# gal-psg-2.net
KiCad netlist of a schematic drawn in EAGLE
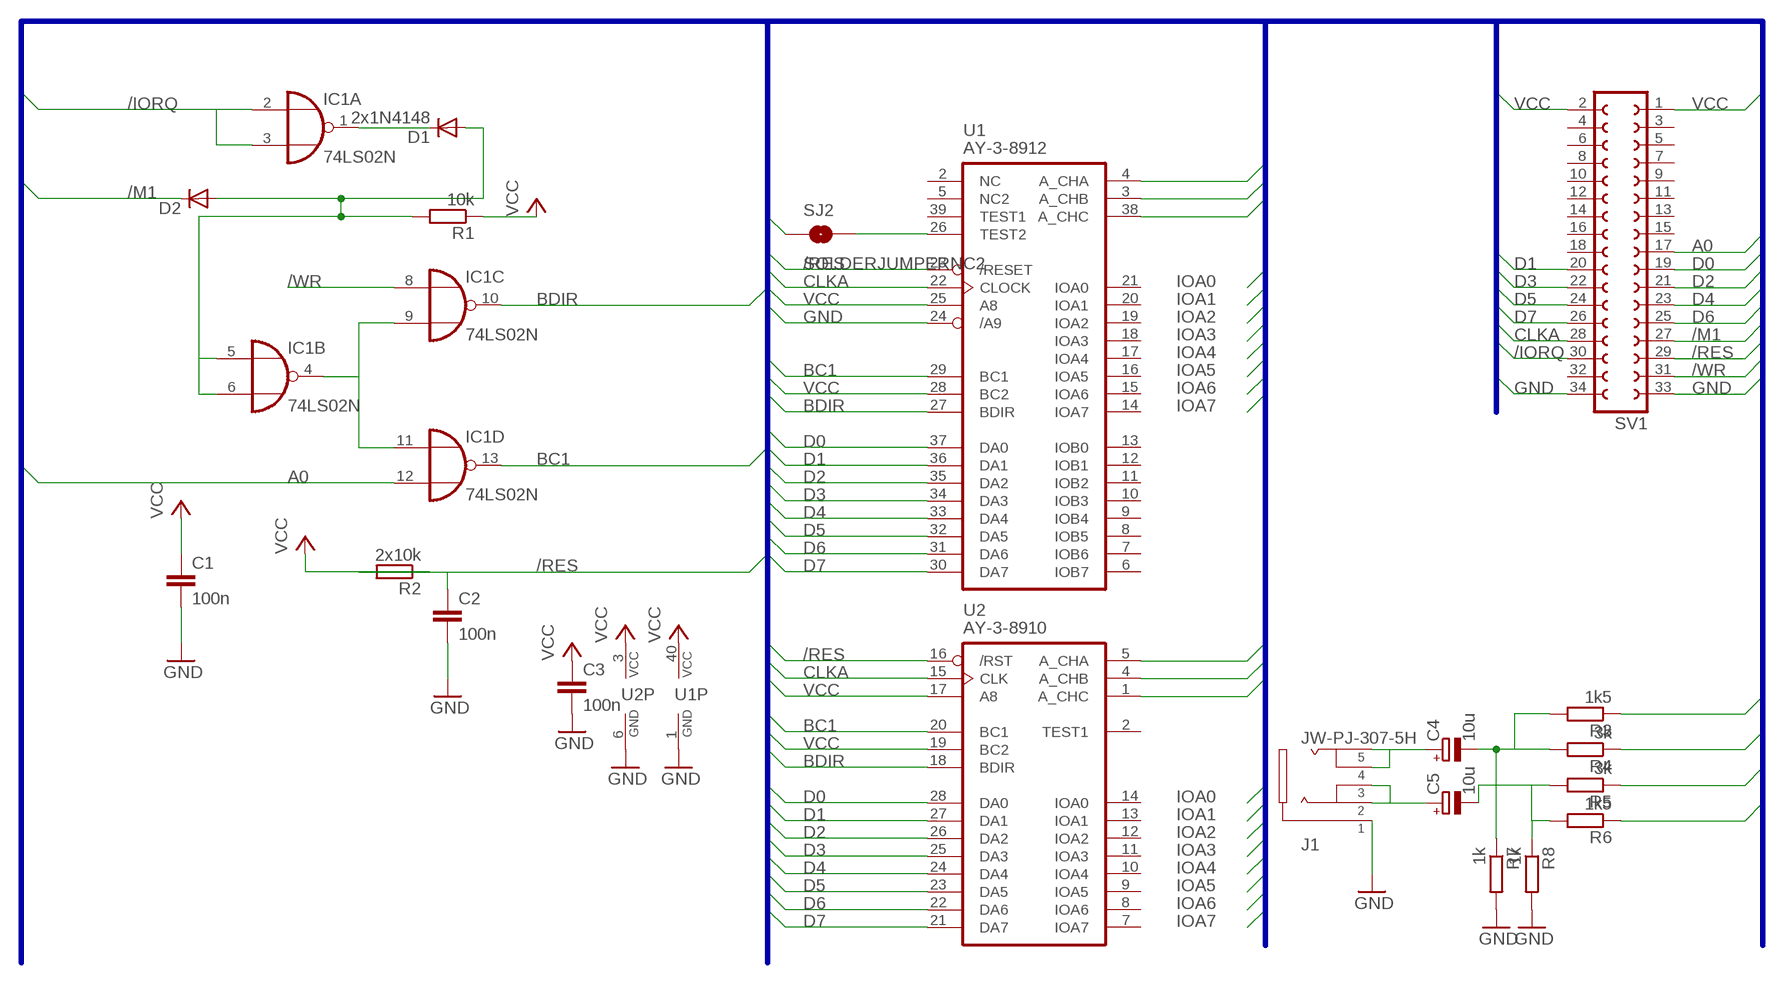
[diagram p0: schematic, sheet 1]

(export (version "E")
  (design (tool "Eeschema 10.0.6"))
  (components
    (comp (ref "C1")
      (value "100n")
      (footprint "eagle-import:C025-024X044")
      (libsource (lib "eagle-import") (part "C-EU025-024X044"))
    )
    (comp (ref "C2")
      (value "100n")
      (footprint "eagle-import:C025-024X044")
      (libsource (lib "eagle-import") (part "C-EU025-024X044"))
    )
    (comp (ref "C3")
      (value "100n")
      (footprint "eagle-import:C025-024X044")
      (libsource (lib "eagle-import") (part "C-EU025-024X044"))
    )
    (comp (ref "C4")
      (value "10u")
      (footprint "eagle-import:E1,8-4")
      (libsource (lib "eagle-import") (part "CPOL-EUE1.8-4"))
    )
    (comp (ref "C5")
      (value "10u")
      (footprint "eagle-import:E1,8-4")
      (libsource (lib "eagle-import") (part "CPOL-EUE1.8-4"))
    )
    (comp (ref "D1")
      (value "2x1N4148")
      (footprint "eagle-import:D-2.5")
      (libsource (lib "eagle-import") (part "DIODE-D-2.5"))
    )
    (comp (ref "D2")
      (value "DIODE-D-2.5")
      (footprint "eagle-import:D-2.5")
      (libsource (lib "eagle-import") (part "DIODE-D-2.5"))
    )
    (comp (ref "IC1")
      (value "74LS02N")
      (footprint "eagle-import:DIL14")
      (libsource (lib "eagle-import") (part "7402NLS"))
    )
    (comp (ref "J1")
      (value "JW-PJ-307-5H")
      (footprint "eagle-import:JW-PJ-307-5H")
      (libsource (lib "eagle-import") (part "JW-PJ-307-5H"))
    )
    (comp (ref "R1")
      (value "10k")
      (footprint "eagle-import:0207_2V")
      (libsource (lib "eagle-import") (part "R-EU_0207/2V"))
    )
    (comp (ref "R2")
      (value "2x10k")
      (footprint "eagle-import:0207_2V")
      (libsource (lib "eagle-import") (part "R-EU_0207/2V"))
    )
    (comp (ref "R3")
      (value "1k5")
      (footprint "eagle-import:0207_2V")
      (libsource (lib "eagle-import") (part "R-EU_0207/2V"))
    )
    (comp (ref "R4")
      (value "3k")
      (footprint "eagle-import:0207_2V")
      (libsource (lib "eagle-import") (part "R-EU_0207/2V"))
    )
    (comp (ref "R5")
      (value "3k")
      (footprint "eagle-import:0207_2V")
      (libsource (lib "eagle-import") (part "R-EU_0207/2V"))
    )
    (comp (ref "R6")
      (value "1k5")
      (footprint "eagle-import:0207_2V")
      (libsource (lib "eagle-import") (part "R-EU_0207/2V"))
    )
    (comp (ref "R7")
      (value "1k")
      (footprint "eagle-import:0207_2V")
      (libsource (lib "eagle-import") (part "R-EU_0207/2V"))
    )
    (comp (ref "R8")
      (value "1k")
      (footprint "eagle-import:0207_2V")
      (libsource (lib "eagle-import") (part "R-EU_0207/2V"))
    )
    (comp (ref "SJ2")
      (value "SOLDERJUMPERNC2")
      (footprint "eagle-import:SJ_2S-NOTRACE")
      (libsource (lib "eagle-import") (part "SOLDERJUMPERNC2"))
    )
    (comp (ref "SV1")
      (value "FE17-2W")
      (footprint "eagle-import:FE17-2W")
      (libsource (lib "eagle-import") (part "FE17-2W"))
    )
    (comp (ref "U1")
      (value "AY-3-8912")
      (footprint "eagle-import:DIL40")
      (libsource (lib "eagle-import") (part "AY-3-8912"))
    )
    (comp (ref "U2")
      (value "AY-3-8910")
      (footprint "eagle-import:DIL28-6")
      (libsource (lib "eagle-import") (part "AY-3-8910"))
    )
  )
  (nets
    (net (code "1") (name "/A") (class "Default")
      (node (ref "R3") (pin "1") (pinfunction "1_1") (pintype "passive"))
      (node (ref "U1") (pin "4") (pinfunction "A_CHA_4") (pintype "output"))
      (node (ref "U2") (pin "5") (pinfunction "A_CHA_5") (pintype "output"))
    )
    (net (code "2") (name "/A0") (class "Default")
      (node (ref "IC1") (pin "12") (pinfunction "I1_12") (pintype "input"))
      (node (ref "SV1") (pin "17") (pinfunction "17_17") (pintype "passive"))
    )
    (net (code "3") (name "/B") (class "Default")
      (node (ref "R4") (pin "1") (pinfunction "1_1") (pintype "passive"))
      (node (ref "R5") (pin "1") (pinfunction "1_1") (pintype "passive"))
      (node (ref "U1") (pin "3") (pinfunction "A_CHB_3") (pintype "output"))
      (node (ref "U2") (pin "4") (pinfunction "A_CHB_4") (pintype "output"))
    )
    (net (code "4") (name "/BC1") (class "Default")
      (node (ref "IC1") (pin "13") (pinfunction "O_13") (pintype "output"))
      (node (ref "U1") (pin "29") (pinfunction "BC1_29") (pintype "input"))
      (node (ref "U2") (pin "20") (pinfunction "BC1_20") (pintype "input"))
    )
    (net (code "5") (name "/BDIR") (class "Default")
      (node (ref "IC1") (pin "10") (pinfunction "O_10") (pintype "output"))
      (node (ref "U1") (pin "27") (pinfunction "BDIR_27") (pintype "input"))
      (node (ref "U2") (pin "18") (pinfunction "BDIR_18") (pintype "input"))
    )
    (net (code "6") (name "/C") (class "Default")
      (node (ref "R6") (pin "1") (pinfunction "1_1") (pintype "passive"))
      (node (ref "U1") (pin "38") (pinfunction "A_CHC_38") (pintype "output"))
      (node (ref "U2") (pin "1") (pinfunction "A_CHC_1") (pintype "output"))
    )
    (net (code "7") (name "/CLKA") (class "Default")
      (node (ref "SV1") (pin "28") (pinfunction "28_28") (pintype "passive"))
      (node (ref "U1") (pin "22") (pinfunction "CLOCK_22") (pintype "input"))
      (node (ref "U2") (pin "15") (pinfunction "CLK_15") (pintype "input"))
    )
    (net (code "8") (name "/D0") (class "Default")
      (node (ref "SV1") (pin "19") (pinfunction "19_19") (pintype "passive"))
      (node (ref "U1") (pin "37") (pinfunction "DA0_37") (pintype "bidirectional"))
      (node (ref "U2") (pin "28") (pinfunction "DA0_28") (pintype "bidirectional"))
    )
    (net (code "9") (name "/D1") (class "Default")
      (node (ref "SV1") (pin "20") (pinfunction "20_20") (pintype "passive"))
      (node (ref "U1") (pin "36") (pinfunction "DA1_36") (pintype "bidirectional"))
      (node (ref "U2") (pin "27") (pinfunction "DA1_27") (pintype "bidirectional"))
    )
    (net (code "10") (name "/D2") (class "Default")
      (node (ref "SV1") (pin "21") (pinfunction "21_21") (pintype "passive"))
      (node (ref "U1") (pin "35") (pinfunction "DA2_35") (pintype "bidirectional"))
      (node (ref "U2") (pin "26") (pinfunction "DA2_26") (pintype "bidirectional"))
    )
    (net (code "11") (name "/D3") (class "Default")
      (node (ref "SV1") (pin "22") (pinfunction "22_22") (pintype "passive"))
      (node (ref "U1") (pin "34") (pinfunction "DA3_34") (pintype "bidirectional"))
      (node (ref "U2") (pin "25") (pinfunction "DA3_25") (pintype "bidirectional"))
    )
    (net (code "12") (name "/D4") (class "Default")
      (node (ref "SV1") (pin "23") (pinfunction "23_23") (pintype "passive"))
      (node (ref "U1") (pin "33") (pinfunction "DA4_33") (pintype "bidirectional"))
      (node (ref "U2") (pin "24") (pinfunction "DA4_24") (pintype "bidirectional"))
    )
    (net (code "13") (name "/D5") (class "Default")
      (node (ref "SV1") (pin "24") (pinfunction "24_24") (pintype "passive"))
      (node (ref "U1") (pin "32") (pinfunction "DA5_32") (pintype "bidirectional"))
      (node (ref "U2") (pin "23") (pinfunction "DA5_23") (pintype "bidirectional"))
    )
    (net (code "14") (name "/D6") (class "Default")
      (node (ref "SV1") (pin "25") (pinfunction "25_25") (pintype "passive"))
      (node (ref "U1") (pin "31") (pinfunction "DA6_31") (pintype "bidirectional"))
      (node (ref "U2") (pin "22") (pinfunction "DA6_22") (pintype "bidirectional"))
    )
    (net (code "15") (name "/D7") (class "Default")
      (node (ref "SV1") (pin "26") (pinfunction "26_26") (pintype "passive"))
      (node (ref "U1") (pin "30") (pinfunction "DA7_30") (pintype "bidirectional"))
      (node (ref "U2") (pin "21") (pinfunction "DA7_21") (pintype "bidirectional"))
    )
    (net (code "24") (name "/{slash}IORQ") (class "Default")
      (node (ref "IC1") (pin "2") (pinfunction "I0_2") (pintype "input"))
      (node (ref "IC1") (pin "3") (pinfunction "I1_3") (pintype "input"))
      (node (ref "SV1") (pin "30") (pinfunction "30_30") (pintype "passive"))
    )
    (net (code "25") (name "/{slash}M1") (class "Default")
      (node (ref "D2") (pin "C") (pinfunction "C_C") (pintype "passive"))
      (node (ref "SV1") (pin "27") (pinfunction "27_27") (pintype "passive"))
    )
    (net (code "26") (name "/{slash}RES") (class "Default")
      (node (ref "C2") (pin "1") (pinfunction "1_1") (pintype "passive"))
      (node (ref "R2") (pin "2") (pinfunction "2_2") (pintype "passive"))
      (node (ref "SV1") (pin "29") (pinfunction "29_29") (pintype "passive"))
      (node (ref "U1") (pin "23") (pinfunction "/RESET_23") (pintype "input"))
      (node (ref "U2") (pin "16") (pinfunction "/RST_16") (pintype "input"))
    )
    (net (code "27") (name "/{slash}WR") (class "Default")
      (node (ref "IC1") (pin "8") (pinfunction "I0_8") (pintype "input"))
      (node (ref "SV1") (pin "31") (pinfunction "31_31") (pintype "passive"))
    )
    (net (code "28") (name "GND") (class "Default")
      (node (ref "C1") (pin "2") (pinfunction "2_2") (pintype "passive"))
      (node (ref "C2") (pin "2") (pinfunction "2_2") (pintype "passive"))
      (node (ref "C3") (pin "2") (pinfunction "2_2") (pintype "passive"))
      (node (ref "J1") (pin "1") (pinfunction "1_1") (pintype "passive"))
      (node (ref "R7") (pin "2") (pinfunction "2_2") (pintype "passive"))
      (node (ref "R8") (pin "2") (pinfunction "2_2") (pintype "passive"))
      (node (ref "SJ2") (pin "1") (pinfunction "1_1") (pintype "passive"))
      (node (ref "SV1") (pin "33") (pinfunction "33_33") (pintype "passive"))
      (node (ref "SV1") (pin "34") (pinfunction "34_34") (pintype "passive"))
      (node (ref "U1") (pin "1") (pinfunction "GND_1") (pintype "power_in"))
      (node (ref "U1") (pin "24") (pinfunction "/A9_24") (pintype "input"))
      (node (ref "U2") (pin "6") (pinfunction "GND_6") (pintype "power_in"))
    )
    (net (code "29") (name "Net-(C4-Pad+)") (class "Default")
      (node (ref "C4") (pin "+") (pinfunction "+_+") (pintype "passive"))
      (node (ref "J1") (pin "4") (pinfunction "4_4") (pintype "passive"))
      (node (ref "J1") (pin "5") (pinfunction "5_5") (pintype "passive"))
    )
    (net (code "30") (name "Net-(C4-Pad-)") (class "Default")
      (node (ref "C4") (pin "-") (pinfunction "-_-") (pintype "passive"))
      (node (ref "R3") (pin "2") (pinfunction "2_2") (pintype "passive"))
      (node (ref "R4") (pin "2") (pinfunction "2_2") (pintype "passive"))
      (node (ref "R7") (pin "1") (pinfunction "1_1") (pintype "passive"))
    )
    (net (code "31") (name "Net-(C5-Pad+)") (class "Default")
      (node (ref "C5") (pin "+") (pinfunction "+_+") (pintype "passive"))
      (node (ref "J1") (pin "2") (pinfunction "2_2") (pintype "passive"))
      (node (ref "J1") (pin "3") (pinfunction "3_3") (pintype "passive"))
    )
    (net (code "32") (name "Net-(C5-Pad-)") (class "Default")
      (node (ref "C5") (pin "-") (pinfunction "-_-") (pintype "passive"))
      (node (ref "R5") (pin "2") (pinfunction "2_2") (pintype "passive"))
      (node (ref "R6") (pin "2") (pinfunction "2_2") (pintype "passive"))
      (node (ref "R8") (pin "1") (pinfunction "1_1") (pintype "passive"))
    )
    (net (code "33") (name "Net-(IC1A-O)") (class "Default")
      (node (ref "D1") (pin "C") (pinfunction "C_C") (pintype "passive"))
      (node (ref "IC1") (pin "1") (pinfunction "O_1") (pintype "output"))
    )
    (net (code "34") (name "Net-(IC1B-I0)") (class "Default")
      (node (ref "D1") (pin "A") (pinfunction "A_A") (pintype "passive"))
      (node (ref "D2") (pin "A") (pinfunction "A_A") (pintype "passive"))
      (node (ref "IC1") (pin "5") (pinfunction "I0_5") (pintype "input"))
      (node (ref "IC1") (pin "6") (pinfunction "I1_6") (pintype "input"))
      (node (ref "R1") (pin "2") (pinfunction "2_2") (pintype "passive"))
    )
    (net (code "35") (name "Net-(IC1B-O)") (class "Default")
      (node (ref "IC1") (pin "11") (pinfunction "I0_11") (pintype "input"))
      (node (ref "IC1") (pin "4") (pinfunction "O_4") (pintype "output"))
      (node (ref "IC1") (pin "9") (pinfunction "I1_9") (pintype "input"))
    )
    (net (code "36") (name "Net-(U1A-TEST2)") (class "Default")
      (node (ref "SJ2") (pin "2") (pinfunction "2_2") (pintype "passive"))
      (node (ref "U1") (pin "26") (pinfunction "TEST2_26") (pintype "input"))
    )
    (net (code "37") (name "VCC") (class "Default")
      (node (ref "C1") (pin "1") (pinfunction "1_1") (pintype "passive"))
      (node (ref "C3") (pin "1") (pinfunction "1_1") (pintype "passive"))
      (node (ref "R1") (pin "1") (pinfunction "1_1") (pintype "passive"))
      (node (ref "R2") (pin "1") (pinfunction "1_1") (pintype "passive"))
      (node (ref "SV1") (pin "1") (pinfunction "1_1") (pintype "passive"))
      (node (ref "SV1") (pin "2") (pinfunction "2_2") (pintype "passive"))
      (node (ref "U1") (pin "25") (pinfunction "A8_25") (pintype "input"))
      (node (ref "U1") (pin "28") (pinfunction "BC2_28") (pintype "input"))
      (node (ref "U1") (pin "40") (pinfunction "VCC_40") (pintype "power_in"))
      (node (ref "U2") (pin "17") (pinfunction "A8_17") (pintype "input"))
      (node (ref "U2") (pin "19") (pinfunction "BC2_19") (pintype "input"))
      (node (ref "U2") (pin "3") (pinfunction "VCC_3") (pintype "power_in"))
    )
    (net (code "38") (name "unconnected-(SV1-Pad3)") (class "Default")
      (node (ref "SV1") (pin "3") (pinfunction "3_3") (pintype "passive"))
    )
    (net (code "39") (name "unconnected-(SV1-Pad4)") (class "Default")
      (node (ref "SV1") (pin "4") (pinfunction "4_4") (pintype "passive"))
    )
    (net (code "40") (name "unconnected-(SV1-Pad5)") (class "Default")
      (node (ref "SV1") (pin "5") (pinfunction "5_5") (pintype "passive"))
    )
    (net (code "41") (name "unconnected-(SV1-Pad6)") (class "Default")
      (node (ref "SV1") (pin "6") (pinfunction "6_6") (pintype "passive"))
    )
    (net (code "42") (name "unconnected-(SV1-Pad7)") (class "Default")
      (node (ref "SV1") (pin "7") (pinfunction "7_7") (pintype "passive"))
    )
    (net (code "43") (name "unconnected-(SV1-Pad8)") (class "Default")
      (node (ref "SV1") (pin "8") (pinfunction "8_8") (pintype "passive"))
    )
    (net (code "44") (name "unconnected-(SV1-Pad9)") (class "Default")
      (node (ref "SV1") (pin "9") (pinfunction "9_9") (pintype "passive"))
    )
    (net (code "45") (name "unconnected-(SV1-Pad10)") (class "Default")
      (node (ref "SV1") (pin "10") (pinfunction "10_10") (pintype "passive"))
    )
    (net (code "46") (name "unconnected-(SV1-Pad11)") (class "Default")
      (node (ref "SV1") (pin "11") (pinfunction "11_11") (pintype "passive"))
    )
    (net (code "47") (name "unconnected-(SV1-Pad12)") (class "Default")
      (node (ref "SV1") (pin "12") (pinfunction "12_12") (pintype "passive"))
    )
    (net (code "48") (name "unconnected-(SV1-Pad13)") (class "Default")
      (node (ref "SV1") (pin "13") (pinfunction "13_13") (pintype "passive"))
    )
    (net (code "49") (name "unconnected-(SV1-Pad14)") (class "Default")
      (node (ref "SV1") (pin "14") (pinfunction "14_14") (pintype "passive"))
    )
    (net (code "50") (name "unconnected-(SV1-Pad15)") (class "Default")
      (node (ref "SV1") (pin "15") (pinfunction "15_15") (pintype "passive"))
    )
    (net (code "51") (name "unconnected-(SV1-Pad16)") (class "Default")
      (node (ref "SV1") (pin "16") (pinfunction "16_16") (pintype "passive"))
    )
    (net (code "52") (name "unconnected-(SV1-Pad18)") (class "Default")
      (node (ref "SV1") (pin "18") (pinfunction "18_18") (pintype "passive"))
    )
    (net (code "53") (name "unconnected-(SV1-Pad32)") (class "Default")
      (node (ref "SV1") (pin "32") (pinfunction "32_32") (pintype "passive"))
    )
    (net (code "54") (name "unconnected-(U1A-IOA0-Pad21)") (class "Default")
      (node (ref "U1") (pin "21") (pinfunction "IOA0_21") (pintype "bidirectional"))
    )
    (net (code "55") (name "unconnected-(U1A-IOA1-Pad20)") (class "Default")
      (node (ref "U1") (pin "20") (pinfunction "IOA1_20") (pintype "bidirectional"))
    )
    (net (code "56") (name "unconnected-(U1A-IOA2-Pad19)") (class "Default")
      (node (ref "U1") (pin "19") (pinfunction "IOA2_19") (pintype "bidirectional"))
    )
    (net (code "57") (name "unconnected-(U1A-IOA3-Pad18)") (class "Default")
      (node (ref "U1") (pin "18") (pinfunction "IOA3_18") (pintype "bidirectional"))
    )
    (net (code "58") (name "unconnected-(U1A-IOA4-Pad17)") (class "Default")
      (node (ref "U1") (pin "17") (pinfunction "IOA4_17") (pintype "bidirectional"))
    )
    (net (code "59") (name "unconnected-(U1A-IOA5-Pad16)") (class "Default")
      (node (ref "U1") (pin "16") (pinfunction "IOA5_16") (pintype "bidirectional"))
    )
    (net (code "60") (name "unconnected-(U1A-IOA6-Pad15)") (class "Default")
      (node (ref "U1") (pin "15") (pinfunction "IOA6_15") (pintype "bidirectional"))
    )
    (net (code "61") (name "unconnected-(U1A-IOA7-Pad14)") (class "Default")
      (node (ref "U1") (pin "14") (pinfunction "IOA7_14") (pintype "bidirectional"))
    )
    (net (code "62") (name "unconnected-(U1A-IOB0-Pad13)") (class "Default")
      (node (ref "U1") (pin "13") (pinfunction "IOB0_13") (pintype "bidirectional"))
    )
    (net (code "63") (name "unconnected-(U1A-IOB1-Pad12)") (class "Default")
      (node (ref "U1") (pin "12") (pinfunction "IOB1_12") (pintype "bidirectional"))
    )
    (net (code "64") (name "unconnected-(U1A-IOB2-Pad11)") (class "Default")
      (node (ref "U1") (pin "11") (pinfunction "IOB2_11") (pintype "bidirectional"))
    )
    (net (code "65") (name "unconnected-(U1A-IOB3-Pad10)") (class "Default")
      (node (ref "U1") (pin "10") (pinfunction "IOB3_10") (pintype "bidirectional"))
    )
    (net (code "66") (name "unconnected-(U1A-IOB4-Pad9)") (class "Default")
      (node (ref "U1") (pin "9") (pinfunction "IOB4_9") (pintype "bidirectional"))
    )
    (net (code "67") (name "unconnected-(U1A-IOB5-Pad8)") (class "Default")
      (node (ref "U1") (pin "8") (pinfunction "IOB5_8") (pintype "bidirectional"))
    )
    (net (code "68") (name "unconnected-(U1A-IOB6-Pad7)") (class "Default")
      (node (ref "U1") (pin "7") (pinfunction "IOB6_7") (pintype "bidirectional"))
    )
    (net (code "69") (name "unconnected-(U1A-IOB7-Pad6)") (class "Default")
      (node (ref "U1") (pin "6") (pinfunction "IOB7_6") (pintype "bidirectional"))
    )
    (net (code "70") (name "unconnected-(U1A-NC-Pad2)") (class "Default")
      (node (ref "U1") (pin "2") (pinfunction "NC_2") (pintype "no_connect"))
    )
    (net (code "71") (name "unconnected-(U1A-NC2-Pad5)") (class "Default")
      (node (ref "U1") (pin "5") (pinfunction "NC2_5") (pintype "no_connect"))
    )
    (net (code "72") (name "unconnected-(U1A-TEST1-Pad39)") (class "Default")
      (node (ref "U1") (pin "39") (pinfunction "TEST1_39") (pintype "input"))
    )
    (net (code "73") (name "unconnected-(U2A-IOA0-Pad14)") (class "Default")
      (node (ref "U2") (pin "14") (pinfunction "IOA0_14") (pintype "bidirectional"))
    )
    (net (code "74") (name "unconnected-(U2A-IOA1-Pad13)") (class "Default")
      (node (ref "U2") (pin "13") (pinfunction "IOA1_13") (pintype "bidirectional"))
    )
    (net (code "75") (name "unconnected-(U2A-IOA2-Pad12)") (class "Default")
      (node (ref "U2") (pin "12") (pinfunction "IOA2_12") (pintype "bidirectional"))
    )
    (net (code "76") (name "unconnected-(U2A-IOA3-Pad11)") (class "Default")
      (node (ref "U2") (pin "11") (pinfunction "IOA3_11") (pintype "bidirectional"))
    )
    (net (code "77") (name "unconnected-(U2A-IOA4-Pad10)") (class "Default")
      (node (ref "U2") (pin "10") (pinfunction "IOA4_10") (pintype "bidirectional"))
    )
    (net (code "78") (name "unconnected-(U2A-IOA5-Pad9)") (class "Default")
      (node (ref "U2") (pin "9") (pinfunction "IOA5_9") (pintype "bidirectional"))
    )
    (net (code "79") (name "unconnected-(U2A-IOA6-Pad8)") (class "Default")
      (node (ref "U2") (pin "8") (pinfunction "IOA6_8") (pintype "bidirectional"))
    )
    (net (code "80") (name "unconnected-(U2A-IOA7-Pad7)") (class "Default")
      (node (ref "U2") (pin "7") (pinfunction "IOA7_7") (pintype "bidirectional"))
    )
    (net (code "81") (name "unconnected-(U2A-TEST1-Pad2)") (class "Default")
      (node (ref "U2") (pin "2") (pinfunction "TEST1_2") (pintype "input"))
    )
  )
)
